# Schematic.net
KiCad netlist of a schematic drawn in EasyEDA
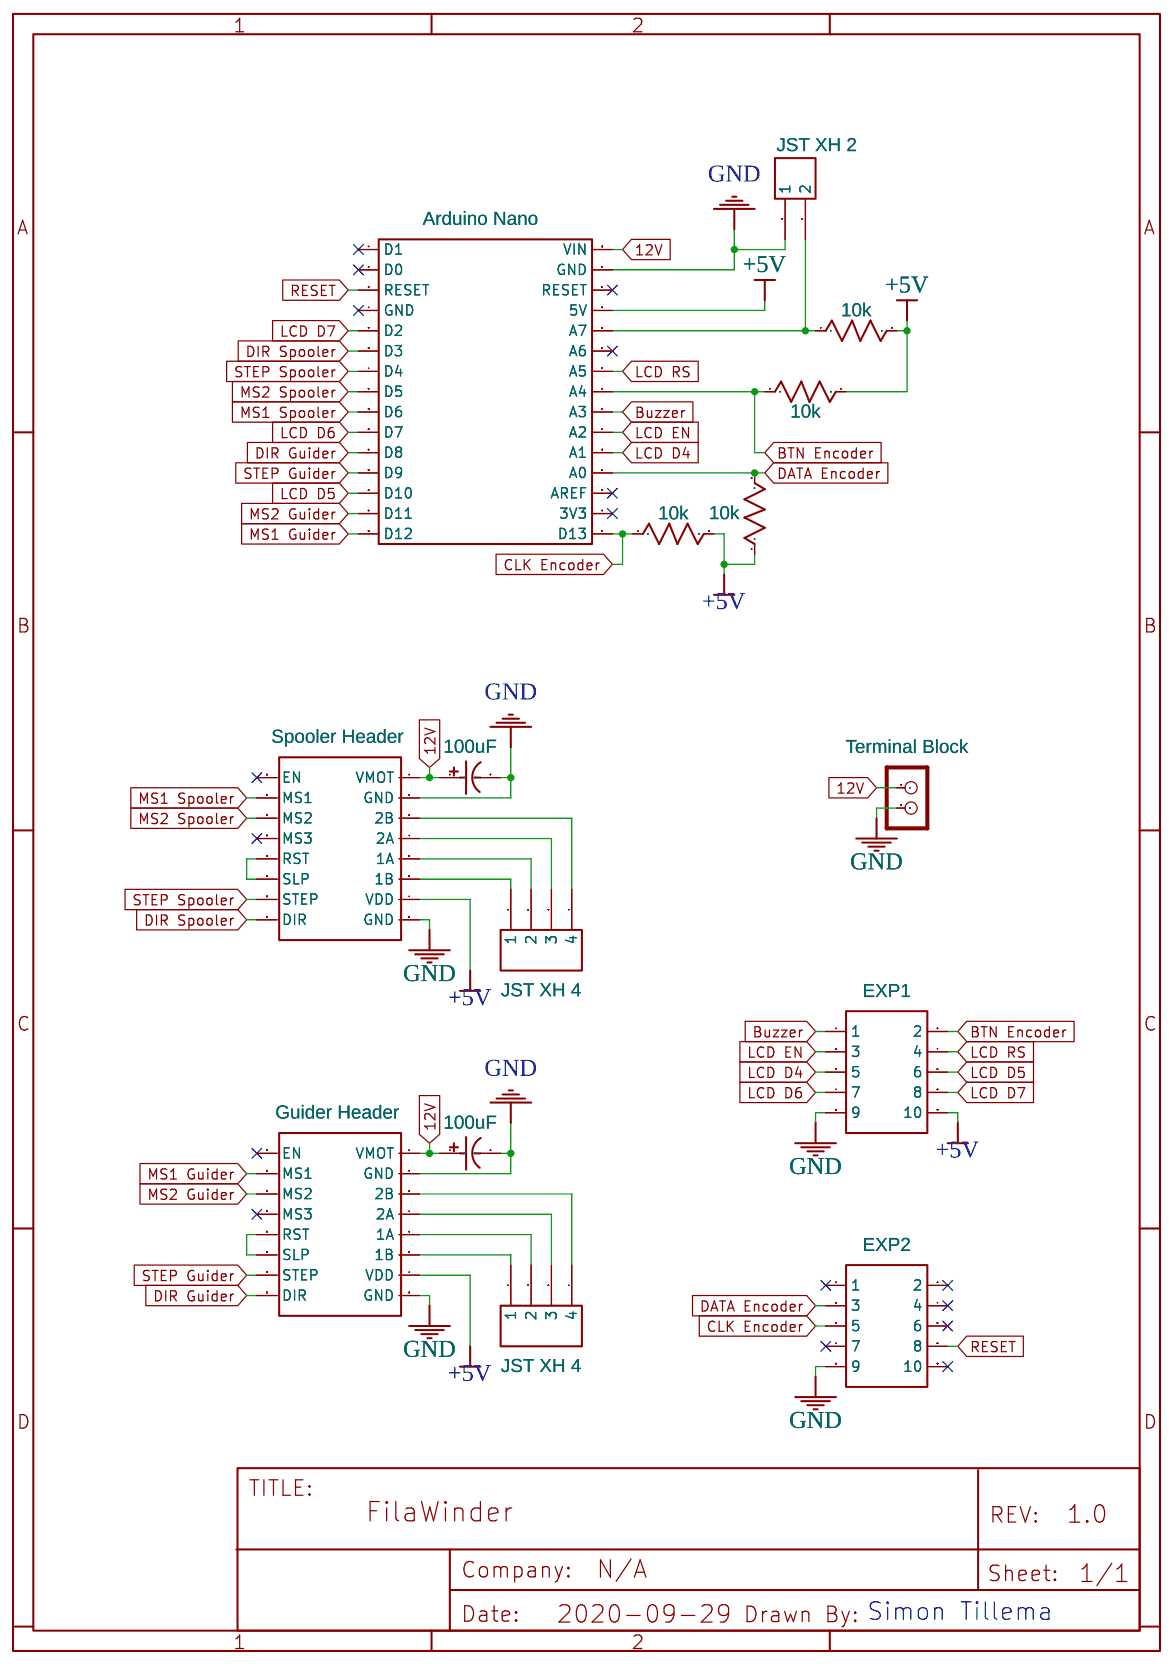
[diagram p0: schematic sheet]

(export (version "E")
  (design (tool "Eeschema 10.0.6"))
  (components
    (comp (ref "C1")
      (value "100uF")
      (fields (field (name "BOM_Manufacturer Part") "100uF 25V") (field (name "BOM_Supplier Part") "C13376"))
      (libsource (lib "") (part "100uF 25V"))
    )
    (comp (ref "C3")
      (value "100uF")
      (fields (field (name "BOM_Manufacturer Part") "100uF 25V") (field (name "BOM_Supplier Part") "C13376"))
      (libsource (lib "") (part "100uF 25V"))
    )
    (comp (ref "CN1")
      (value "JST XH 4")
      (fields (field (name "BOM_Manufacturer Part") "XH-4A") (field (name "BOM_Supplier Part") "C37815"))
      (libsource (lib "") (part "XH-4A"))
    )
    (comp (ref "CN2")
      (value "JST XH 4")
      (fields (field (name "BOM_Manufacturer Part") "XH-4A") (field (name "BOM_Supplier Part") "C37815"))
      (libsource (lib "") (part "XH-4A"))
    )
    (comp (ref "CN3")
      (value "JST XH 2")
      (fields (field (name "BOM_Manufacturer Part") "XH-2A") (field (name "BOM_Supplier Part") "C20079"))
      (libsource (lib "") (part "XH-2A"))
    )
    (comp (ref "J1") (value "Arduino Nano") (libsource (lib "") (part "Arduino_Nano_Header")))
    (comp (ref "J2") (value "Terminal Block") (libsource (lib "") (part "CON_TERMINAL_BLOCK_02-5MM")))
    (comp (ref "R1") (value "10k") (libsource (lib "") (part "R_0603_US")))
    (comp (ref "R2") (value "10k") (libsource (lib "") (part "R_0603_US_1")))
    (comp (ref "R3") (value "10k") (libsource (lib "") (part "R_0603_US_1")))
    (comp (ref "R5") (value "10k") (libsource (lib "") (part "R_0603_US_1")))
    (comp (ref "U1")
      (value "Spooler Header")
      (fields
        (field (name "BOM_Manufacturer Part") "A4988 Stepper Motor Driver Carrier")
        (field (name "BOM_Supplier Part") "1182")
      )
      (libsource (lib "") (part "A4988 Board"))
    )
    (comp (ref "U2")
      (value "Guider Header")
      (fields
        (field (name "BOM_Manufacturer Part") "A4988 Stepper Motor Driver Carrier")
        (field (name "BOM_Supplier Part") "1182")
      )
      (libsource (lib "") (part "A4988 Board"))
    )
    (comp (ref "U3") (value "EXP1") (libsource (lib "") (part "10pin header")))
    (comp (ref "U4") (value "EXP2") (libsource (lib "") (part "10pin header")))
  )
  (nets
    (net (code "1") (name "+5V") (class "Default")
      (node (ref "J1") (pin "27") (pinfunction "5V_27") (pintype "unspecified"))
      (node (ref "R1") (pin "1") (pinfunction "1_1") (pintype "unspecified"))
      (node (ref "R2") (pin "2") (pinfunction "2_2") (pintype "unspecified"))
      (node (ref "R3") (pin "2") (pinfunction "2_2") (pintype "unspecified"))
      (node (ref "R5") (pin "2") (pinfunction "2_2") (pintype "unspecified"))
      (node (ref "U1") (pin "7") (pinfunction "VDD_7") (pintype "unspecified"))
      (node (ref "U2") (pin "7") (pinfunction "VDD_7") (pintype "unspecified"))
      (node (ref "U3") (pin "10") (pinfunction "10_10") (pintype "unspecified"))
    )
    (net (code "2") (name "12V") (class "Default")
      (node (ref "C1") (pin "1") (pinfunction "1_1") (pintype "input"))
      (node (ref "C3") (pin "1") (pinfunction "1_1") (pintype "input"))
      (node (ref "J1") (pin "30") (pinfunction "VIN_30") (pintype "unspecified"))
      (node (ref "J2") (pin "1") (pinfunction "1_1") (pintype "unspecified"))
      (node (ref "U1") (pin "1") (pinfunction "VMOT_1") (pintype "unspecified"))
      (node (ref "U2") (pin "1") (pinfunction "VMOT_1") (pintype "unspecified"))
    )
    (net (code "3") (name "BTN Encoder") (class "Default")
      (node (ref "J1") (pin "23") (pinfunction "A4_23") (pintype "unspecified"))
      (node (ref "R3") (pin "1") (pinfunction "1_1") (pintype "unspecified"))
      (node (ref "U3") (pin "2") (pinfunction "2_2") (pintype "unspecified"))
    )
    (net (code "4") (name "Buzzer") (class "Default")
      (node (ref "J1") (pin "22") (pinfunction "A3_22") (pintype "unspecified"))
      (node (ref "U3") (pin "1") (pinfunction "1_1") (pintype "unspecified"))
    )
    (net (code "5") (name "CLK Encoder") (class "Default")
      (node (ref "J1") (pin "16") (pinfunction "D13_16") (pintype "unspecified"))
      (node (ref "R2") (pin "1") (pinfunction "1_1") (pintype "unspecified"))
      (node (ref "U4") (pin "5") (pinfunction "5_5") (pintype "unspecified"))
    )
    (net (code "6") (name "DATA Encoder") (class "Default")
      (node (ref "J1") (pin "19") (pinfunction "A0_19") (pintype "unspecified"))
      (node (ref "R1") (pin "2") (pinfunction "2_2") (pintype "unspecified"))
      (node (ref "U4") (pin "3") (pinfunction "3_3") (pintype "unspecified"))
    )
    (net (code "7") (name "DIR Guider") (class "Default")
      (node (ref "J1") (pin "11") (pinfunction "D8_11") (pintype "unspecified"))
      (node (ref "U2") (pin "16") (pinfunction "DIR_16") (pintype "unspecified"))
    )
    (net (code "8") (name "DIR Spooler") (class "Default")
      (node (ref "J1") (pin "6") (pinfunction "D3_6") (pintype "unspecified"))
      (node (ref "U1") (pin "16") (pinfunction "DIR_16") (pintype "unspecified"))
    )
    (net (code "9") (name "GND") (class "Default")
      (node (ref "C1") (pin "2") (pinfunction "2_2") (pintype "input"))
      (node (ref "C3") (pin "2") (pinfunction "2_2") (pintype "input"))
      (node (ref "CN3") (pin "1") (pinfunction "1_1") (pintype "unspecified"))
      (node (ref "J1") (pin "29") (pinfunction "GND_29") (pintype "unspecified"))
      (node (ref "J2") (pin "2") (pinfunction "2_2") (pintype "unspecified"))
      (node (ref "U1") (pin "2") (pinfunction "GND_2") (pintype "unspecified"))
      (node (ref "U1") (pin "8") (pinfunction "GND_8") (pintype "unspecified"))
      (node (ref "U2") (pin "2") (pinfunction "GND_2") (pintype "unspecified"))
      (node (ref "U2") (pin "8") (pinfunction "GND_8") (pintype "unspecified"))
      (node (ref "U3") (pin "9") (pinfunction "9_9") (pintype "unspecified"))
      (node (ref "U4") (pin "9") (pinfunction "9_9") (pintype "unspecified"))
    )
    (net (code "10") (name "LCD D4") (class "Default")
      (node (ref "J1") (pin "20") (pinfunction "A1_20") (pintype "unspecified"))
      (node (ref "U3") (pin "5") (pinfunction "5_5") (pintype "unspecified"))
    )
    (net (code "11") (name "LCD D5") (class "Default")
      (node (ref "J1") (pin "13") (pinfunction "D10_13") (pintype "unspecified"))
      (node (ref "U3") (pin "6") (pinfunction "6_6") (pintype "unspecified"))
    )
    (net (code "12") (name "LCD D6") (class "Default")
      (node (ref "J1") (pin "10") (pinfunction "D7_10") (pintype "unspecified"))
      (node (ref "U3") (pin "7") (pinfunction "7_7") (pintype "unspecified"))
    )
    (net (code "13") (name "LCD D7") (class "Default")
      (node (ref "J1") (pin "5") (pinfunction "D2_5") (pintype "unspecified"))
      (node (ref "U3") (pin "8") (pinfunction "8_8") (pintype "unspecified"))
    )
    (net (code "14") (name "LCD EN") (class "Default")
      (node (ref "J1") (pin "21") (pinfunction "A2_21") (pintype "unspecified"))
      (node (ref "U3") (pin "3") (pinfunction "3_3") (pintype "unspecified"))
    )
    (net (code "15") (name "LCD RS") (class "Default")
      (node (ref "J1") (pin "24") (pinfunction "A5_24") (pintype "unspecified"))
      (node (ref "U3") (pin "4") (pinfunction "4_4") (pintype "unspecified"))
    )
    (net (code "16") (name "MS1 Guider") (class "Default")
      (node (ref "J1") (pin "15") (pinfunction "D12_15") (pintype "unspecified"))
      (node (ref "U2") (pin "10") (pinfunction "MS1_10") (pintype "unspecified"))
    )
    (net (code "17") (name "MS1 Spooler") (class "Default")
      (node (ref "J1") (pin "9") (pinfunction "D6_9") (pintype "unspecified"))
      (node (ref "U1") (pin "10") (pinfunction "MS1_10") (pintype "unspecified"))
    )
    (net (code "18") (name "MS2 Guider") (class "Default")
      (node (ref "J1") (pin "14") (pinfunction "D11_14") (pintype "unspecified"))
      (node (ref "U2") (pin "11") (pinfunction "MS2_11") (pintype "unspecified"))
    )
    (net (code "19") (name "MS2 Spooler") (class "Default")
      (node (ref "J1") (pin "8") (pinfunction "D5_8") (pintype "unspecified"))
      (node (ref "U1") (pin "11") (pinfunction "MS2_11") (pintype "unspecified"))
    )
    (net (code "20") (name "Net-(J1-A7)") (class "Default")
      (node (ref "CN3") (pin "2") (pinfunction "2_2") (pintype "unspecified"))
      (node (ref "J1") (pin "26") (pinfunction "A7_26") (pintype "unspecified"))
      (node (ref "R5") (pin "1") (pinfunction "1_1") (pintype "unspecified"))
    )
    (net (code "21") (name "Net-(U1-1A)") (class "Default")
      (node (ref "CN2") (pin "2") (pinfunction "2_2") (pintype "unspecified"))
      (node (ref "U1") (pin "5") (pinfunction "1A_5") (pintype "unspecified"))
    )
    (net (code "22") (name "Net-(U1-1B)") (class "Default")
      (node (ref "CN2") (pin "1") (pinfunction "1_1") (pintype "unspecified"))
      (node (ref "U1") (pin "6") (pinfunction "1B_6") (pintype "unspecified"))
    )
    (net (code "23") (name "Net-(U1-2A)") (class "Default")
      (node (ref "CN2") (pin "3") (pinfunction "3_3") (pintype "unspecified"))
      (node (ref "U1") (pin "4") (pinfunction "2A_4") (pintype "unspecified"))
    )
    (net (code "24") (name "Net-(U1-2B)") (class "Default")
      (node (ref "CN2") (pin "4") (pinfunction "4_4") (pintype "unspecified"))
      (node (ref "U1") (pin "3") (pinfunction "2B_3") (pintype "unspecified"))
    )
    (net (code "25") (name "Net-(U1-RST)") (class "Default")
      (node (ref "U1") (pin "13") (pinfunction "RST_13") (pintype "unspecified"))
      (node (ref "U1") (pin "14") (pinfunction "SLP_14") (pintype "unspecified"))
    )
    (net (code "26") (name "Net-(U2-1A)") (class "Default")
      (node (ref "CN1") (pin "2") (pinfunction "2_2") (pintype "unspecified"))
      (node (ref "U2") (pin "5") (pinfunction "1A_5") (pintype "unspecified"))
    )
    (net (code "27") (name "Net-(U2-1B)") (class "Default")
      (node (ref "CN1") (pin "1") (pinfunction "1_1") (pintype "unspecified"))
      (node (ref "U2") (pin "6") (pinfunction "1B_6") (pintype "unspecified"))
    )
    (net (code "28") (name "Net-(U2-2A)") (class "Default")
      (node (ref "CN1") (pin "3") (pinfunction "3_3") (pintype "unspecified"))
      (node (ref "U2") (pin "4") (pinfunction "2A_4") (pintype "unspecified"))
    )
    (net (code "29") (name "Net-(U2-2B)") (class "Default")
      (node (ref "CN1") (pin "4") (pinfunction "4_4") (pintype "unspecified"))
      (node (ref "U2") (pin "3") (pinfunction "2B_3") (pintype "unspecified"))
    )
    (net (code "30") (name "Net-(U2-RST)") (class "Default")
      (node (ref "U2") (pin "13") (pinfunction "RST_13") (pintype "unspecified"))
      (node (ref "U2") (pin "14") (pinfunction "SLP_14") (pintype "unspecified"))
    )
    (net (code "31") (name "RESET") (class "Default")
      (node (ref "J1") (pin "3") (pinfunction "RESET_3") (pintype "unspecified"))
      (node (ref "U4") (pin "8") (pinfunction "8_8") (pintype "unspecified"))
    )
    (net (code "32") (name "STEP Guider") (class "Default")
      (node (ref "J1") (pin "12") (pinfunction "D9_12") (pintype "unspecified"))
      (node (ref "U2") (pin "15") (pinfunction "STEP_15") (pintype "unspecified"))
    )
    (net (code "33") (name "STEP Spooler") (class "Default")
      (node (ref "J1") (pin "7") (pinfunction "D4_7") (pintype "unspecified"))
      (node (ref "U1") (pin "15") (pinfunction "STEP_15") (pintype "unspecified"))
    )
    (net (code "34") (name "unconnected-(J1-3V3-Pad17)") (class "Default")
      (node (ref "J1") (pin "17") (pinfunction "3V3_17") (pintype "unspecified+no_connect"))
    )
    (net (code "35") (name "unconnected-(J1-A6-Pad25)") (class "Default")
      (node (ref "J1") (pin "25") (pinfunction "A6_25") (pintype "unspecified+no_connect"))
    )
    (net (code "36") (name "unconnected-(J1-AREF-Pad18)") (class "Default")
      (node (ref "J1") (pin "18") (pinfunction "AREF_18") (pintype "unspecified+no_connect"))
    )
    (net (code "37") (name "unconnected-(J1-D0-Pad2)") (class "Default")
      (node (ref "J1") (pin "2") (pinfunction "D0_2") (pintype "unspecified+no_connect"))
    )
    (net (code "38") (name "unconnected-(J1-D1-Pad1)") (class "Default")
      (node (ref "J1") (pin "1") (pinfunction "D1_1") (pintype "unspecified+no_connect"))
    )
    (net (code "39") (name "unconnected-(J1-GND-Pad4)") (class "Default")
      (node (ref "J1") (pin "4") (pinfunction "GND_4") (pintype "unspecified+no_connect"))
    )
    (net (code "40") (name "unconnected-(J1-RESET-Pad28)") (class "Default")
      (node (ref "J1") (pin "28") (pinfunction "RESET_28") (pintype "unspecified+no_connect"))
    )
    (net (code "41") (name "unconnected-(U1-EN-Pad9)") (class "Default")
      (node (ref "U1") (pin "9") (pinfunction "EN_9") (pintype "unspecified+no_connect"))
    )
    (net (code "42") (name "unconnected-(U1-MS3-Pad12)") (class "Default")
      (node (ref "U1") (pin "12") (pinfunction "MS3_12") (pintype "unspecified+no_connect"))
    )
    (net (code "43") (name "unconnected-(U2-EN-Pad9)") (class "Default")
      (node (ref "U2") (pin "9") (pinfunction "EN_9") (pintype "unspecified+no_connect"))
    )
    (net (code "44") (name "unconnected-(U2-MS3-Pad12)") (class "Default")
      (node (ref "U2") (pin "12") (pinfunction "MS3_12") (pintype "unspecified+no_connect"))
    )
    (net (code "45") (name "unconnected-(U4-Pad1)") (class "Default")
      (node (ref "U4") (pin "1") (pinfunction "1_1") (pintype "unspecified+no_connect"))
    )
    (net (code "46") (name "unconnected-(U4-Pad2)") (class "Default")
      (node (ref "U4") (pin "2") (pinfunction "2_2") (pintype "unspecified+no_connect"))
    )
    (net (code "47") (name "unconnected-(U4-Pad4)") (class "Default")
      (node (ref "U4") (pin "4") (pinfunction "4_4") (pintype "unspecified+no_connect"))
    )
    (net (code "48") (name "unconnected-(U4-Pad6)") (class "Default")
      (node (ref "U4") (pin "6") (pinfunction "6_6") (pintype "unspecified+no_connect"))
    )
    (net (code "49") (name "unconnected-(U4-Pad7)") (class "Default")
      (node (ref "U4") (pin "7") (pinfunction "7_7") (pintype "unspecified+no_connect"))
    )
    (net (code "50") (name "unconnected-(U4-Pad10)") (class "Default")
      (node (ref "U4") (pin "10") (pinfunction "10_10") (pintype "unspecified+no_connect"))
    )
  )
)
